# Sheet2.net
KiCad netlist of a schematic drawn in Altium Designer
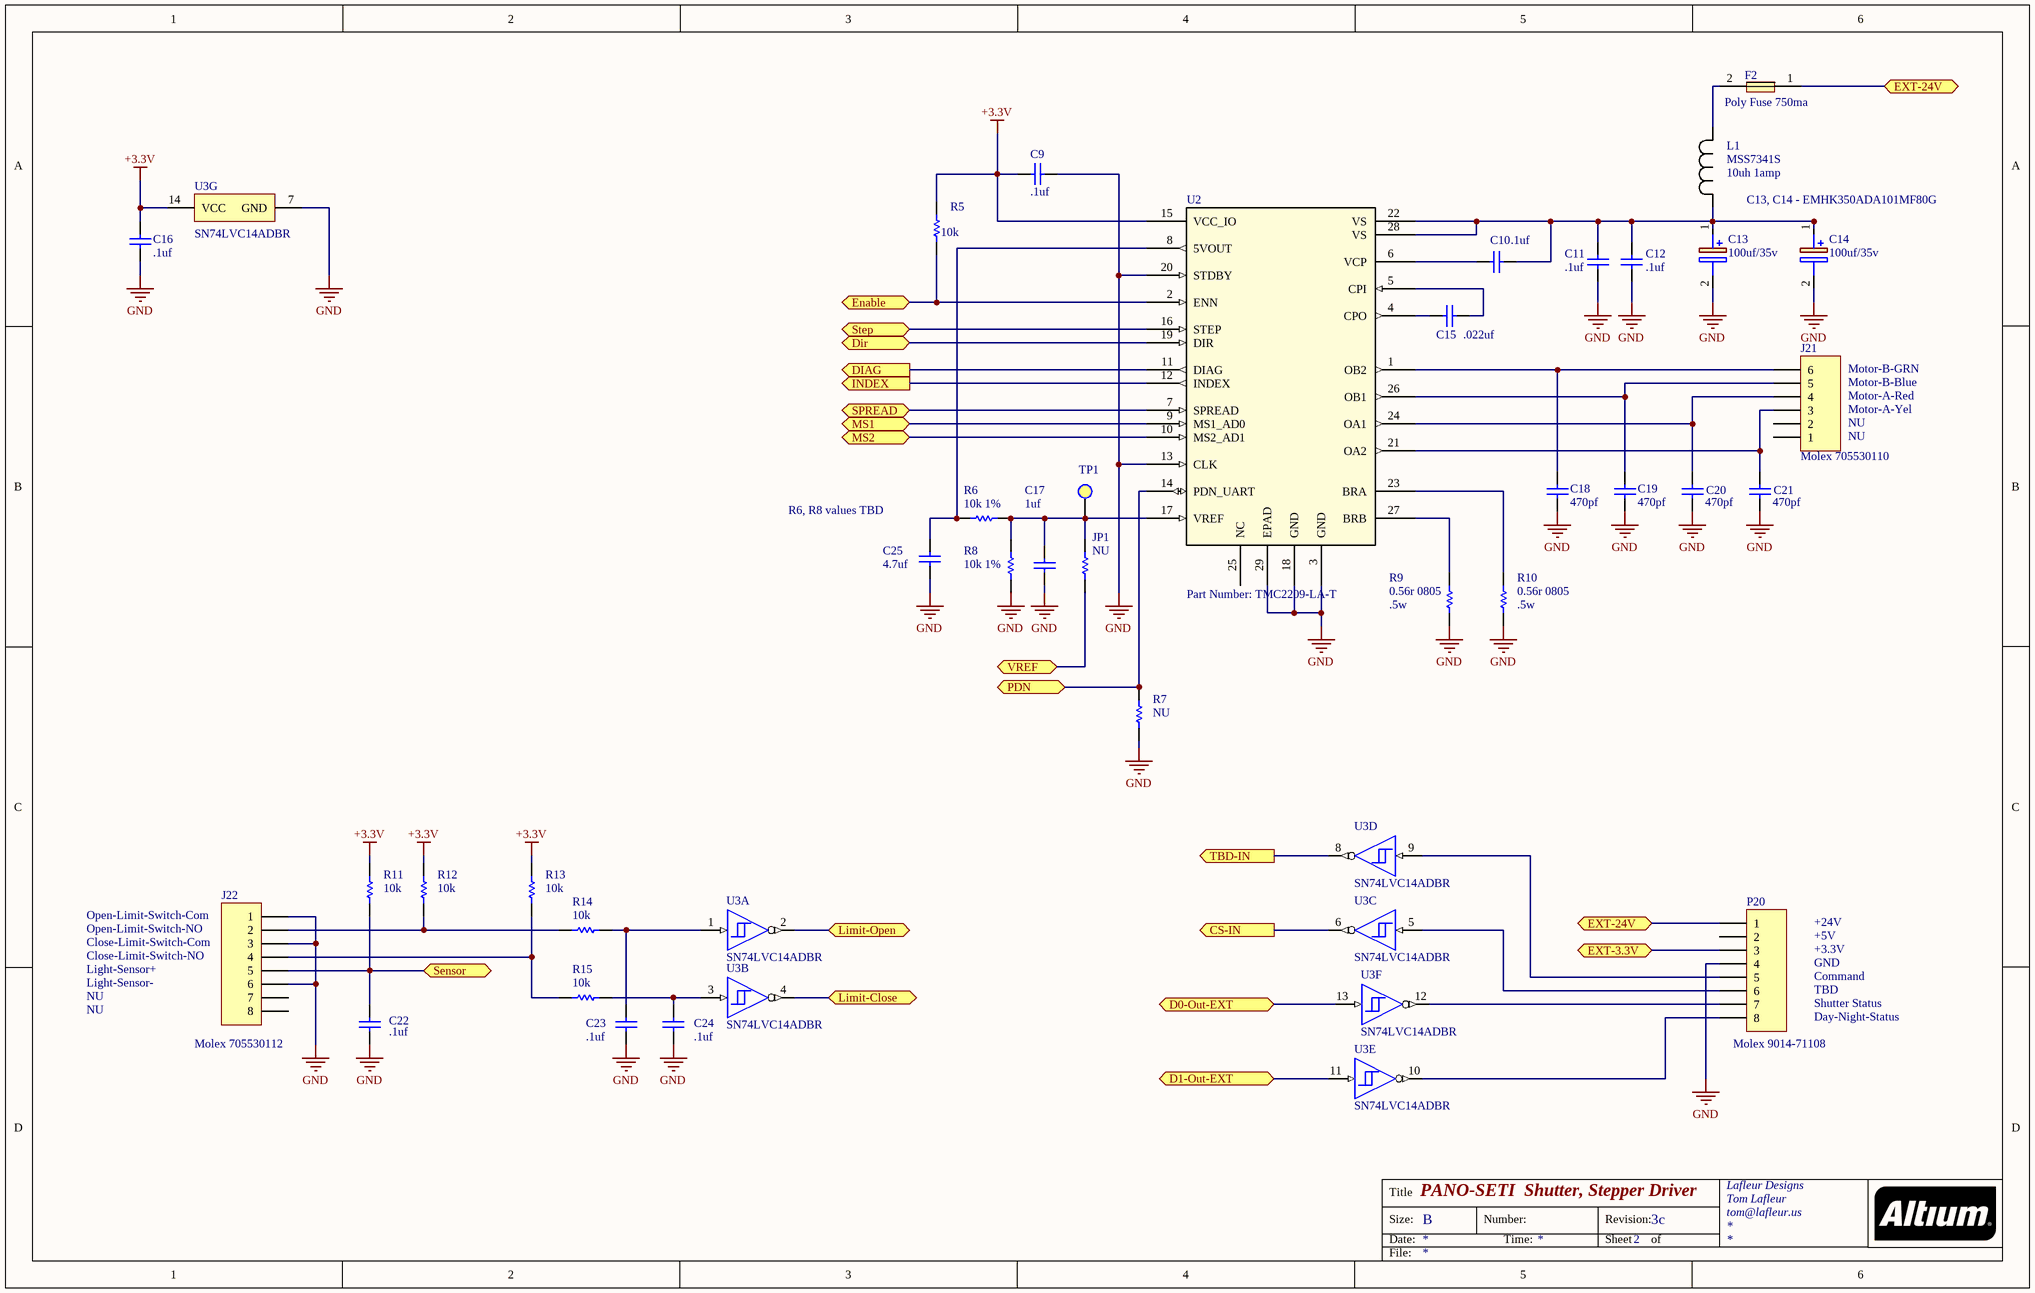
[diagram p0: Sheet2.SchDoc]

(export (version "E")
  (design (tool "Eeschema 10.0.6"))
  (components
    (comp (ref "C9")
      (value ".1uf")
      (footprint "6-0805")
      (description "Capacitor")
      (libsource (lib "Winmor-Demo-R2") (part "CAP_2"))
    )
    (comp (ref "C10")
      (value ".1uf")
      (footprint "6-0805")
      (description "Capacitor")
      (libsource (lib "Winmor-Demo-R2") (part "CAP_2"))
    )
    (comp (ref "C11")
      (value ".1uf")
      (footprint "6-0805")
      (description "Capacitor")
      (libsource (lib "Winmor-Demo-R2") (part "CAP_2"))
    )
    (comp (ref "C12")
      (value ".1uf")
      (footprint "6-0805")
      (description "Capacitor")
      (libsource (lib "Winmor-Demo-R2") (part "CAP_2"))
    )
    (comp (ref "C13")
      (value "100uf/35v")
      (footprint "SamacSys:CAPAE660X610N")
      (description "Capacitor Polarised")
      (fields
        (field (name "MANUFACTURER_PART_NUMBER") "EEE-FT1V101AP")
        (field (name "MOUSER PART NUMBER") "667-EEE-FT1V101AP")
      )
      (libsource (lib "*") (part "EEE-FT1V101AP"))
    )
    (comp (ref "C14")
      (value "100uf/35v")
      (footprint "SamacSys:CAPAE660X610N")
      (description "Capacitor Polarised")
      (fields
        (field (name "MANUFACTURER_PART_NUMBER") "EEE-FT1V101AP")
        (field (name "MOUSER PART NUMBER") "667-EEE-FT1V101AP")
      )
      (libsource (lib "*") (part "EEE-FT1V101AP"))
    )
    (comp (ref "C15")
      (value ".022uf")
      (footprint "6-0805")
      (description "Capacitor")
      (libsource (lib "Winmor-Demo-R2") (part "CAP_2"))
    )
    (comp (ref "C16")
      (value ".1uf")
      (footprint "6-0805")
      (description "Capacitor")
      (libsource (lib "Winmor-Demo-R2") (part "CAP_2"))
    )
    (comp (ref "C17")
      (value "1uf")
      (footprint "6-0805")
      (description "Capacitor")
      (libsource (lib "Winmor-Demo-R2") (part "CAP_2"))
    )
    (comp (ref "C18")
      (value "470pf")
      (footprint "6-0805")
      (description "Capacitor")
      (libsource (lib "Winmor-Demo-R2") (part "CAP_2"))
    )
    (comp (ref "C19")
      (value "470pf")
      (footprint "6-0805")
      (description "Capacitor")
      (libsource (lib "Winmor-Demo-R2") (part "CAP_2"))
    )
    (comp (ref "C20")
      (value "470pf")
      (footprint "6-0805")
      (description "Capacitor")
      (libsource (lib "Winmor-Demo-R2") (part "CAP_2"))
    )
    (comp (ref "C21")
      (value "470pf")
      (footprint "6-0805")
      (description "Capacitor")
      (libsource (lib "Winmor-Demo-R2") (part "CAP_2"))
    )
    (comp (ref "C22")
      (value ".1uf")
      (footprint "6-0805")
      (description "Capacitor")
      (libsource (lib "Winmor-Demo-R2") (part "CAP_2"))
    )
    (comp (ref "C23")
      (value ".1uf")
      (footprint "6-0805")
      (description "Capacitor")
      (libsource (lib "Winmor-Demo-R2") (part "CAP_2"))
    )
    (comp (ref "C24")
      (value ".1uf")
      (footprint "6-0805")
      (description "Capacitor")
      (libsource (lib "Winmor-Demo-R2") (part "CAP_2"))
    )
    (comp (ref "C25")
      (value "4.7uf")
      (footprint "6-0805")
      (description "Capacitor")
      (libsource (lib "Winmor-Demo-R2") (part "CAP_2"))
    )
    (comp (ref "F2")
      (value "Poly Fuse 750ma")
      (footprint "PTC 2016L")
      (description "Poly Fuse")
      (libsource (lib "N2K Project") (part "Poly Fuse"))
    )
    (comp (ref "J21")
      (value "Molex 705530110")
      (footprint "HDR1X6")
      (description "Header, 6-Pin")
      (fields (field (name "PUBLISHER") "Altium Limited"))
      (libsource (lib "Miscellaneous Connectors") (part "Header 6"))
    )
    (comp (ref "J22")
      (value "Molex 705530112")
      (footprint "HDR1X8")
      (description "Header, 8-Pin")
      (fields (field (name "PUBLISHER") "Altium Limited"))
      (libsource (lib "Miscellaneous Connectors") (part "Header 8"))
    )
    (comp (ref "JP1")
      (value "NU")
      (footprint "6-0805")
      (description "Precision Thick Film Chip Resistor, 10 Ohm to 2.2M Ohm Range, 1% Tolerance, 1206 Size, 0.125 W")
      (fields (field (name "PUBLISHER") "Altium Limited"))
      (libsource (lib "N2K Project") (part "ERJ8EN"))
    )
    (comp (ref "L1")
      (value "MSS7341S")
      (footprint "MSS7341502NLD")
      (description "No Description Available")
      (fields
        (field (name "MANUFACTURER_PART_NUMBER") "SRU1048-101Y")
        (field (name "COPYRIGHT") "Copyright (C) 2018 Accelerated Designs. All rights reserved")
      )
      (libsource (lib "2019-11-24_16-49-35") (part "SRU1048-101Y"))
    )
    (comp (ref "P20")
      (value "Molex 9014-71108")
      (footprint "HDR1X8")
      (description "Header, 8-Pin")
      (fields (field (name "PUBLISHER") "Altium Limited"))
      (libsource (lib "") (part "Header 8_1"))
    )
    (comp (ref "R5")
      (value "10k")
      (footprint "6-0805")
      (description "Precision Thick Film Chip Resistor, 10 Ohm to 2.2M Ohm Range, 1% Tolerance, 1206 Size, 0.125 W")
      (fields (field (name "PUBLISHER") "Altium Limited"))
      (libsource (lib "N2K Project") (part "ERJ8EN"))
    )
    (comp (ref "R6")
      (value "10k 1%")
      (footprint "6-0805")
      (description "Precision Thick Film Chip Resistor, 10 Ohm to 2.2M Ohm Range, 1% Tolerance, 1206 Size, 0.125 W")
      (fields (field (name "PUBLISHER") "Altium Limited"))
      (libsource (lib "N2K Project") (part "ERJ8EN"))
    )
    (comp (ref "R7")
      (value "NU")
      (footprint "6-0805")
      (description "Precision Thick Film Chip Resistor, 10 Ohm to 2.2M Ohm Range, 1% Tolerance, 1206 Size, 0.125 W")
      (fields (field (name "PUBLISHER") "Altium Limited"))
      (libsource (lib "N2K Project") (part "ERJ8EN"))
    )
    (comp (ref "R8")
      (value "10k 1%")
      (footprint "6-0805")
      (description "Precision Thick Film Chip Resistor, 10 Ohm to 2.2M Ohm Range, 1% Tolerance, 1206 Size, 0.125 W")
      (fields (field (name "PUBLISHER") "Altium Limited"))
      (libsource (lib "N2K Project") (part "ERJ8EN"))
    )
    (comp (ref "R9")
      (value "0.56r 0805")
      (footprint "6-0805")
      (description "Precision Thick Film Chip Resistor, 10 Ohm to 2.2M Ohm Range, 1% Tolerance, 1206 Size, 0.125 W")
      (fields (field (name "PUBLISHER") "Altium Limited"))
      (libsource (lib "N2K Project") (part "ERJ8EN"))
    )
    (comp (ref "R10")
      (value "0.56r 0805")
      (footprint "6-0805")
      (description "Precision Thick Film Chip Resistor, 10 Ohm to 2.2M Ohm Range, 1% Tolerance, 1206 Size, 0.125 W")
      (fields (field (name "PUBLISHER") "Altium Limited"))
      (libsource (lib "N2K Project") (part "ERJ8EN"))
    )
    (comp (ref "R11")
      (value "10k")
      (footprint "6-0805")
      (description "Precision Thick Film Chip Resistor, 10 Ohm to 2.2M Ohm Range, 1% Tolerance, 1206 Size, 0.125 W")
      (fields (field (name "PUBLISHER") "Altium Limited"))
      (libsource (lib "N2K Project") (part "ERJ8EN"))
    )
    (comp (ref "R12")
      (value "10k")
      (footprint "6-0805")
      (description "Precision Thick Film Chip Resistor, 10 Ohm to 2.2M Ohm Range, 1% Tolerance, 1206 Size, 0.125 W")
      (fields (field (name "PUBLISHER") "Altium Limited"))
      (libsource (lib "N2K Project") (part "ERJ8EN"))
    )
    (comp (ref "R13")
      (value "10k")
      (footprint "6-0805")
      (description "Precision Thick Film Chip Resistor, 10 Ohm to 2.2M Ohm Range, 1% Tolerance, 1206 Size, 0.125 W")
      (fields (field (name "PUBLISHER") "Altium Limited"))
      (libsource (lib "N2K Project") (part "ERJ8EN"))
    )
    (comp (ref "R14")
      (value "10k")
      (footprint "6-0805")
      (description "Precision Thick Film Chip Resistor, 10 Ohm to 2.2M Ohm Range, 1% Tolerance, 1206 Size, 0.125 W")
      (fields (field (name "PUBLISHER") "Altium Limited"))
      (libsource (lib "N2K Project") (part "ERJ8EN"))
    )
    (comp (ref "R15")
      (value "10k")
      (footprint "6-0805")
      (description "Precision Thick Film Chip Resistor, 10 Ohm to 2.2M Ohm Range, 1% Tolerance, 1206 Size, 0.125 W")
      (fields (field (name "PUBLISHER") "Altium Limited"))
      (libsource (lib "N2K Project") (part "ERJ8EN"))
    )
    (comp (ref "TP1")
      (value "TestPoint")
      (footprint "PCB111:Test Point-Thru-Hole")
      (libsource (lib "Seti-Controler-1a_1") (part "TestPoint"))
    )
    (comp (ref "U2")
      (value "Part Number: TMC2209-LA-T")
      (footprint "QFN50P500X500X90-29N")
      (description "No Description Available")
      (fields
        (field (name "MANUFACTURER_PART_NUMBER") "TMC2209-LA-T")
        (field (name "COPYRIGHT") "Copyright (C) 2018 Accelerated Designs. All rights reserved")
      )
      (libsource (lib "Seti-Controler-3") (part "TMC2209-LA-T"))
    )
    (comp (ref "U3")
      (value "SN74LVC14ADBR")
      (footprint "DB0014A_M")
      (description "Hex Schmitt-Trigger Inverter, DB0014A, LARGE T&R")
      (fields
        (field (name "GENERIC PART NUMBER") "SN74LVC14A")
        (field (name "MANUFACTURER") "Texas Instruments")
      )
      (libsource (lib "Altium Content Vault") (part "TI-CD_SNX4XXXXXX4X_19A-14-SCHMITT"))
    )
  )
  (nets
    (net (code "1") (name "+3.3V") (class "Default")
      (node (ref "C16") (pin "2") (pinfunction "2_2") (pintype "passive"))
      (node (ref "C9") (pin "1") (pinfunction "1_1") (pintype "passive"))
      (node (ref "R11") (pin "1") (pinfunction "1_1") (pintype "passive"))
      (node (ref "R12") (pin "1") (pinfunction "1_1") (pintype "passive"))
      (node (ref "R13") (pin "1") (pinfunction "1_1") (pintype "passive"))
      (node (ref "R5") (pin "1") (pinfunction "1_1") (pintype "passive"))
      (node (ref "U2") (pin "15") (pinfunction "VCC_IO_15") (pintype "power_in"))
      (node (ref "U3") (pin "14") (pinfunction "VCC_14") (pintype "power_in"))
    )
    (net (code "2") (name "/CS-IN") (class "Default")
      (node (ref "U3") (pin "6") (pinfunction "~{3Y}_6") (pintype "output"))
    )
    (net (code "3") (name "/D0-Out-EXT") (class "Default")
      (node (ref "U3") (pin "13") (pinfunction "6A_13") (pintype "input"))
    )
    (net (code "4") (name "/D1-Out-EXT") (class "Default")
      (node (ref "U3") (pin "11") (pinfunction "5A_11") (pintype "input"))
    )
    (net (code "5") (name "/DIAG") (class "Default")
      (node (ref "U2") (pin "11") (pinfunction "DIAG_11") (pintype "output"))
    )
    (net (code "6") (name "/Dir") (class "Default")
      (node (ref "U2") (pin "19") (pinfunction "DIR_19") (pintype "input"))
    )
    (net (code "7") (name "/EXT-3.3V") (class "Default")
      (node (ref "P20") (pin "3") (pinfunction "3_3") (pintype "passive"))
    )
    (net (code "8") (name "/EXT-24V") (class "Default")
      (node (ref "F2") (pin "1") (pinfunction "1_1") (pintype "passive"))
      (node (ref "P20") (pin "1") (pinfunction "1_1") (pintype "passive"))
    )
    (net (code "9") (name "/Enable") (class "Default")
      (node (ref "R5") (pin "2") (pinfunction "2_2") (pintype "passive"))
      (node (ref "U2") (pin "2") (pinfunction "ENN_2") (pintype "input"))
    )
    (net (code "10") (name "/INDEX") (class "Default")
      (node (ref "U2") (pin "12") (pinfunction "INDEX_12") (pintype "output"))
    )
    (net (code "11") (name "/Limit-Close") (class "Default")
      (node (ref "U3") (pin "4") (pinfunction "~{2Y}_4") (pintype "output"))
    )
    (net (code "12") (name "/Limit-Open") (class "Default")
      (node (ref "U3") (pin "2") (pinfunction "~{1Y}_2") (pintype "output"))
    )
    (net (code "13") (name "/MS1") (class "Default")
      (node (ref "U2") (pin "9") (pinfunction "MS1_AD0_9") (pintype "input"))
    )
    (net (code "14") (name "/MS2") (class "Default")
      (node (ref "U2") (pin "10") (pinfunction "MS2_AD1_10") (pintype "input"))
    )
    (net (code "15") (name "/PDN") (class "Default")
      (node (ref "R7") (pin "1") (pinfunction "1_1") (pintype "passive"))
      (node (ref "U2") (pin "14") (pinfunction "PDN_UART_14") (pintype "bidirectional"))
    )
    (net (code "16") (name "/SPREAD") (class "Default")
      (node (ref "U2") (pin "7") (pinfunction "SPREAD_7") (pintype "input"))
    )
    (net (code "17") (name "/Sensor") (class "Default")
      (node (ref "C22") (pin "2") (pinfunction "2_2") (pintype "passive"))
      (node (ref "J22") (pin "5") (pinfunction "5_5") (pintype "passive"))
      (node (ref "R11") (pin "2") (pinfunction "2_2") (pintype "passive"))
    )
    (net (code "18") (name "/Step") (class "Default")
      (node (ref "U2") (pin "16") (pinfunction "STEP_16") (pintype "input"))
    )
    (net (code "19") (name "/TBD-IN") (class "Default")
      (node (ref "U3") (pin "8") (pinfunction "~{4Y}_8") (pintype "output"))
    )
    (net (code "20") (name "/VREF") (class "Default")
      (node (ref "JP1") (pin "2") (pinfunction "2_2") (pintype "passive"))
    )
    (net (code "21") (name "GND") (class "Default")
      (node (ref "C11") (pin "2") (pinfunction "2_2") (pintype "passive"))
      (node (ref "C12") (pin "2") (pinfunction "2_2") (pintype "passive"))
      (node (ref "C13") (pin "2") (pinfunction "-_2") (pintype "passive"))
      (node (ref "C14") (pin "2") (pinfunction "-_2") (pintype "passive"))
      (node (ref "C16") (pin "1") (pinfunction "1_1") (pintype "passive"))
      (node (ref "C17") (pin "2") (pinfunction "2_2") (pintype "passive"))
      (node (ref "C18") (pin "2") (pinfunction "2_2") (pintype "passive"))
      (node (ref "C19") (pin "2") (pinfunction "2_2") (pintype "passive"))
      (node (ref "C20") (pin "2") (pinfunction "2_2") (pintype "passive"))
      (node (ref "C21") (pin "2") (pinfunction "2_2") (pintype "passive"))
      (node (ref "C22") (pin "1") (pinfunction "1_1") (pintype "passive"))
      (node (ref "C23") (pin "1") (pinfunction "1_1") (pintype "passive"))
      (node (ref "C24") (pin "1") (pinfunction "1_1") (pintype "passive"))
      (node (ref "C25") (pin "2") (pinfunction "2_2") (pintype "passive"))
      (node (ref "C9") (pin "2") (pinfunction "2_2") (pintype "passive"))
      (node (ref "J22") (pin "1") (pinfunction "1_1") (pintype "passive"))
      (node (ref "J22") (pin "3") (pinfunction "3_3") (pintype "passive"))
      (node (ref "J22") (pin "6") (pinfunction "6_6") (pintype "passive"))
      (node (ref "P20") (pin "4") (pinfunction "4_4") (pintype "passive"))
      (node (ref "R10") (pin "2") (pinfunction "2_2") (pintype "passive"))
      (node (ref "R7") (pin "2") (pinfunction "2_2") (pintype "passive"))
      (node (ref "R8") (pin "2") (pinfunction "2_2") (pintype "passive"))
      (node (ref "R9") (pin "2") (pinfunction "2_2") (pintype "passive"))
      (node (ref "U2") (pin "13") (pinfunction "CLK_13") (pintype "input"))
      (node (ref "U2") (pin "18") (pinfunction "GND_18") (pintype "power_in"))
      (node (ref "U2") (pin "20") (pinfunction "STDBY_20") (pintype "input"))
      (node (ref "U2") (pin "29") (pinfunction "EPAD_29") (pintype "passive"))
      (node (ref "U2") (pin "3") (pinfunction "GND_3") (pintype "power_in"))
      (node (ref "U3") (pin "7") (pinfunction "GND_7") (pintype "power_in"))
    )
    (net (code "22") (name "Net-(C13-+)") (class "Default")
      (node (ref "C10") (pin "2") (pinfunction "2_2") (pintype "passive"))
      (node (ref "C11") (pin "1") (pinfunction "1_1") (pintype "passive"))
      (node (ref "C12") (pin "1") (pinfunction "1_1") (pintype "passive"))
      (node (ref "C13") (pin "1") (pinfunction "+_1") (pintype "passive"))
      (node (ref "C14") (pin "1") (pinfunction "+_1") (pintype "passive"))
      (node (ref "L1") (pin "2") (pinfunction "2_2") (pintype "passive"))
      (node (ref "U2") (pin "22") (pinfunction "VS_22") (pintype "power_in"))
      (node (ref "U2") (pin "28") (pinfunction "VS_28") (pintype "power_in"))
    )
    (net (code "23") (name "Net-(F2-Pad2)") (class "Default")
      (node (ref "F2") (pin "2") (pinfunction "2_2") (pintype "passive"))
      (node (ref "L1") (pin "1") (pinfunction "1_1") (pintype "passive"))
    )
    (net (code "24") (name "Net-(J22-Pad2)") (class "Default")
      (node (ref "J22") (pin "2") (pinfunction "2_2") (pintype "passive"))
      (node (ref "R12") (pin "2") (pinfunction "2_2") (pintype "passive"))
      (node (ref "R14") (pin "1") (pinfunction "1_1") (pintype "passive"))
    )
    (net (code "25") (name "Net-(J22-Pad4)") (class "Default")
      (node (ref "J22") (pin "4") (pinfunction "4_4") (pintype "passive"))
      (node (ref "R13") (pin "2") (pinfunction "2_2") (pintype "passive"))
      (node (ref "R15") (pin "1") (pinfunction "1_1") (pintype "passive"))
    )
    (net (code "26") (name "Net-(TP1-TP?)") (class "Default")
      (node (ref "C17") (pin "1") (pinfunction "1_1") (pintype "passive"))
      (node (ref "JP1") (pin "1") (pinfunction "1_1") (pintype "passive"))
      (node (ref "R6") (pin "2") (pinfunction "2_2") (pintype "passive"))
      (node (ref "R8") (pin "1") (pinfunction "1_1") (pintype "passive"))
      (node (ref "TP1") (pin "1") (pinfunction "TP?_1") (pintype "passive"))
      (node (ref "U2") (pin "17") (pinfunction "VREF_17") (pintype "input"))
    )
    (net (code "27") (name "Net-(U2-5VOUT)") (class "Default")
      (node (ref "C25") (pin "1") (pinfunction "1_1") (pintype "passive"))
      (node (ref "R6") (pin "1") (pinfunction "1_1") (pintype "passive"))
      (node (ref "U2") (pin "8") (pinfunction "5VOUT_8") (pintype "output"))
    )
    (net (code "28") (name "Net-(U2-BRA)") (class "Default")
      (node (ref "R10") (pin "1") (pinfunction "1_1") (pintype "passive"))
      (node (ref "U2") (pin "23") (pinfunction "BRA_23") (pintype "passive"))
    )
    (net (code "29") (name "Net-(U2-BRB)") (class "Default")
      (node (ref "R9") (pin "1") (pinfunction "1_1") (pintype "passive"))
      (node (ref "U2") (pin "27") (pinfunction "BRB_27") (pintype "passive"))
    )
    (net (code "30") (name "Net-(U2-CPI)") (class "Default")
      (node (ref "C15") (pin "2") (pinfunction "2_2") (pintype "passive"))
      (node (ref "U2") (pin "5") (pinfunction "CPI_5") (pintype "input"))
    )
    (net (code "31") (name "Net-(U2-CPO)") (class "Default")
      (node (ref "C15") (pin "1") (pinfunction "1_1") (pintype "passive"))
      (node (ref "U2") (pin "4") (pinfunction "CPO_4") (pintype "output"))
    )
    (net (code "32") (name "Net-(U2-OA1)") (class "Default")
      (node (ref "C20") (pin "1") (pinfunction "1_1") (pintype "passive"))
      (node (ref "J21") (pin "4") (pinfunction "4_4") (pintype "passive"))
      (node (ref "U2") (pin "24") (pinfunction "OA1_24") (pintype "output"))
    )
    (net (code "33") (name "Net-(U2-OA2)") (class "Default")
      (node (ref "C21") (pin "1") (pinfunction "1_1") (pintype "passive"))
      (node (ref "J21") (pin "3") (pinfunction "3_3") (pintype "passive"))
      (node (ref "U2") (pin "21") (pinfunction "OA2_21") (pintype "output"))
    )
    (net (code "34") (name "Net-(U2-OB1)") (class "Default")
      (node (ref "C19") (pin "1") (pinfunction "1_1") (pintype "passive"))
      (node (ref "J21") (pin "5") (pinfunction "5_5") (pintype "passive"))
      (node (ref "U2") (pin "26") (pinfunction "OB1_26") (pintype "output"))
    )
    (net (code "35") (name "Net-(U2-OB2)") (class "Default")
      (node (ref "C18") (pin "1") (pinfunction "1_1") (pintype "passive"))
      (node (ref "J21") (pin "6") (pinfunction "6_6") (pintype "passive"))
      (node (ref "U2") (pin "1") (pinfunction "OB2_1") (pintype "output"))
    )
    (net (code "36") (name "Net-(U2-VCP)") (class "Default")
      (node (ref "C10") (pin "1") (pinfunction "1_1") (pintype "passive"))
      (node (ref "U2") (pin "6") (pinfunction "VCP_6") (pintype "power_in"))
    )
    (net (code "37") (name "Net-(U3A-1A)") (class "Default")
      (node (ref "C23") (pin "2") (pinfunction "2_2") (pintype "passive"))
      (node (ref "R14") (pin "2") (pinfunction "2_2") (pintype "passive"))
      (node (ref "U3") (pin "1") (pinfunction "1A_1") (pintype "input"))
    )
    (net (code "38") (name "Net-(U3B-2A)") (class "Default")
      (node (ref "C24") (pin "2") (pinfunction "2_2") (pintype "passive"))
      (node (ref "R15") (pin "2") (pinfunction "2_2") (pintype "passive"))
      (node (ref "U3") (pin "3") (pinfunction "2A_3") (pintype "input"))
    )
    (net (code "39") (name "Net-(U3C-3A)") (class "Default")
      (node (ref "P20") (pin "6") (pinfunction "6_6") (pintype "passive"))
      (node (ref "U3") (pin "5") (pinfunction "3A_5") (pintype "input"))
    )
    (net (code "40") (name "Net-(U3D-4A)") (class "Default")
      (node (ref "P20") (pin "5") (pinfunction "5_5") (pintype "passive"))
      (node (ref "U3") (pin "9") (pinfunction "4A_9") (pintype "input"))
    )
    (net (code "41") (name "Net-(U3E-~{5Y})") (class "Default")
      (node (ref "P20") (pin "8") (pinfunction "8_8") (pintype "passive"))
      (node (ref "U3") (pin "10") (pinfunction "~{5Y}_10") (pintype "output"))
    )
    (net (code "42") (name "Net-(U3F-~{6Y})") (class "Default")
      (node (ref "P20") (pin "7") (pinfunction "7_7") (pintype "passive"))
      (node (ref "U3") (pin "12") (pinfunction "~{6Y}_12") (pintype "output"))
    )
    (net (code "43") (name "unconnected-(J21-Pad1)") (class "Default")
      (node (ref "J21") (pin "1") (pinfunction "1_1") (pintype "passive"))
    )
    (net (code "44") (name "unconnected-(J21-Pad2)") (class "Default")
      (node (ref "J21") (pin "2") (pinfunction "2_2") (pintype "passive"))
    )
    (net (code "45") (name "unconnected-(J22-Pad7)") (class "Default")
      (node (ref "J22") (pin "7") (pinfunction "7_7") (pintype "passive"))
    )
    (net (code "46") (name "unconnected-(J22-Pad8)") (class "Default")
      (node (ref "J22") (pin "8") (pinfunction "8_8") (pintype "passive"))
    )
    (net (code "47") (name "unconnected-(P20-Pad2)") (class "Default")
      (node (ref "P20") (pin "2") (pinfunction "2_2") (pintype "passive"))
    )
    (net (code "48") (name "unconnected-(U2-NC-Pad25)") (class "Default")
      (node (ref "U2") (pin "25") (pinfunction "NC_25") (pintype "passive"))
    )
  )
)
